# ir_array.net
KiCad netlist of a schematic drawn in Altium Designer
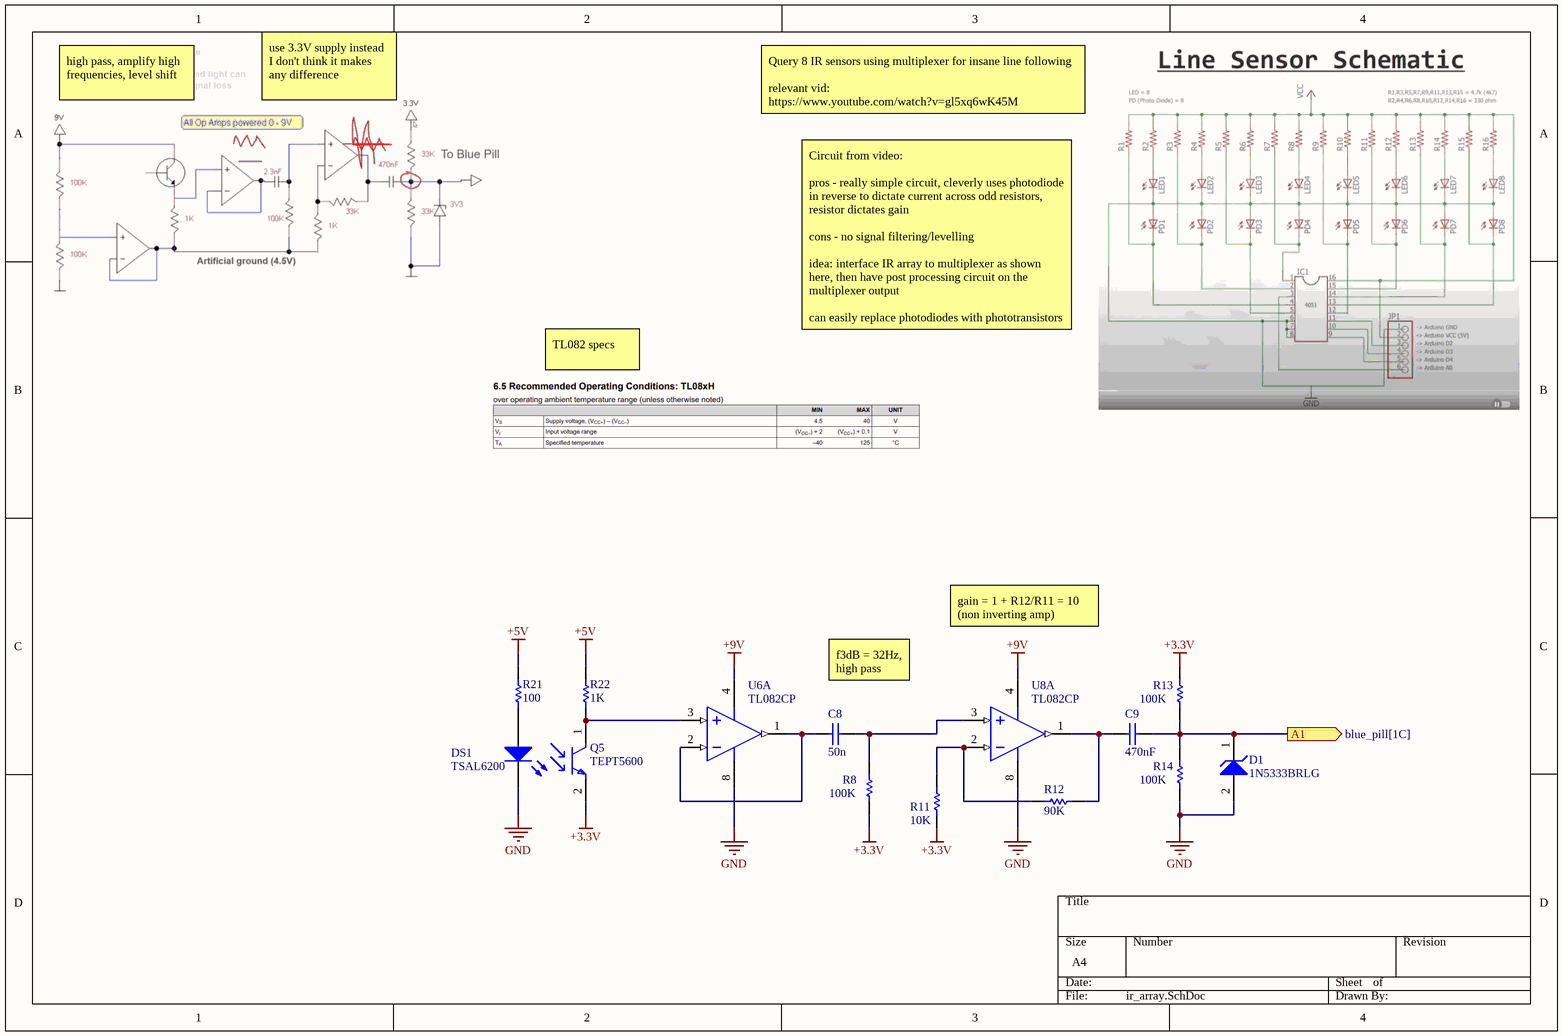
[diagram p0: ir_array.SchDoc]

(export (version "E")
  (design (tool "Eeschema 10.0.6"))
  (components
    (comp (ref "C8")
      (value "50n")
      (description "Capacitor")
      (libsource (lib "Simulation Generic Components") (part "Capacitor"))
    )
    (comp (ref "C9")
      (value "470nF")
      (description "Capacitor")
      (libsource (lib "Simulation Generic Components") (part "Capacitor"))
    )
    (comp (ref "D1")
      (value "1N5333BRLG")
      (footprint "ONSC-SURMETIC40-2-017AA-01")
      (description "5 W Zener Voltage Regulator, 2-Pin Surmetic(TM) 40, Pb-Free, Tape and Reel")
      (fields (field (name "MANUFACTURER") "On Semiconductor"))
      (libsource (lib "Altium Content Vault") (part "ONSC-K1A2-2"))
    )
    (comp (ref "DS1")
      (value "TSAL6200")
      (footprint "VISH-TSAL6200")
      (fields (field (name "MANUFACTURER") "Vishay"))
      (libsource (lib "Altium Content Vault") (part "LED-AK-2"))
    )
    (comp (ref "Q5")
      (value "TEPT5600")
      (footprint "FP-6_544-5185_03-4-MFG")
      (description "SENSOR PHOTO 570NM TOP VIEW RAD")
      (libsource (lib "Altium Content Vault") (part "9456f77f46cf90b3cfae45295d5ca59"))
    )
    (comp (ref "R8")
      (value "100K")
      (description "Resistor")
      (libsource (lib "Simulation Generic Components") (part "Resistor"))
    )
    (comp (ref "R11")
      (value "10K")
      (description "Resistor")
      (libsource (lib "Simulation Generic Components") (part "Resistor"))
    )
    (comp (ref "R12")
      (value "90K")
      (description "Resistor")
      (libsource (lib "Simulation Generic Components") (part "Resistor"))
    )
    (comp (ref "R13")
      (value "100K")
      (description "Resistor")
      (libsource (lib "Simulation Generic Components") (part "Resistor"))
    )
    (comp (ref "R14")
      (value "100K")
      (description "Resistor")
      (libsource (lib "Simulation Generic Components") (part "Resistor"))
    )
    (comp (ref "R21")
      (value "100")
      (description "Resistor")
      (libsource (lib "Simulation Generic Components") (part "Resistor"))
    )
    (comp (ref "R22")
      (value "1K")
      (description "Resistor")
      (libsource (lib "Simulation Generic Components") (part "Resistor"))
    )
    (comp (ref "U6")
      (value "TL082CP")
      (footprint "P0008A")
      (description "JFET-Input Operational Amplifier, 7 to 36 V, 0 to 70 degC, 8-pin DIP (P8), Pb-Free (RoHS)")
      (fields (field (name "MANUFACTURER") "Texas Instruments"))
      (libsource (lib "Altium Content Vault") (part "TI-AMP-D6-2-8_D"))
    )
    (comp (ref "U8")
      (value "TL082CP")
      (footprint "P0008A")
      (description "JFET-Input Operational Amplifier, 7 to 36 V, 0 to 70 degC, 8-pin DIP (P8), Pb-Free (RoHS)")
      (fields (field (name "MANUFACTURER") "Texas Instruments"))
      (libsource (lib "Altium Content Vault") (part "TI-AMP-D6-2-8_D"))
    )
  )
  (nets
    (net (code "1") (name "+3.3V") (class "Default")
      (node (ref "Q5") (pin "2") (pinfunction "E_2") (pintype "passive"))
      (node (ref "R11") (pin "2") (pinfunction "2_2") (pintype "passive"))
      (node (ref "R13") (pin "1") (pinfunction "1_1") (pintype "passive"))
      (node (ref "R8") (pin "2") (pinfunction "2_2") (pintype "passive"))
    )
    (net (code "2") (name "+5V") (class "Default")
      (node (ref "R21") (pin "1") (pinfunction "1_1") (pintype "passive"))
      (node (ref "R22") (pin "1") (pinfunction "1_1") (pintype "passive"))
    )
    (net (code "3") (name "+9V") (class "Default")
      (node (ref "U6") (pin "4") (pinfunction "VCC-_4") (pintype "power_in"))
      (node (ref "U8") (pin "4") (pinfunction "VCC-_4") (pintype "power_in"))
    )
    (net (code "4") (name "/A1") (class "Default")
      (node (ref "C9") (pin "2") (pinfunction "2_2") (pintype "passive"))
      (node (ref "D1") (pin "1") (pinfunction "K_1") (pintype "passive"))
      (node (ref "R13") (pin "2") (pinfunction "2_2") (pintype "passive"))
      (node (ref "R14") (pin "1") (pinfunction "1_1") (pintype "passive"))
    )
    (net (code "5") (name "GND") (class "Default")
      (node (ref "D1") (pin "2") (pinfunction "A_2") (pintype "passive"))
      (node (ref "DS1") (pin "2") (pinfunction "K_2") (pintype "passive"))
      (node (ref "R14") (pin "2") (pinfunction "2_2") (pintype "passive"))
      (node (ref "U6") (pin "8") (pinfunction "VCC+_8") (pintype "power_in"))
      (node (ref "U8") (pin "8") (pinfunction "VCC+_8") (pintype "power_in"))
    )
    (net (code "6") (name "Net-(DS1-A)") (class "Default")
      (node (ref "DS1") (pin "1") (pinfunction "A_1") (pintype "passive"))
      (node (ref "R21") (pin "2") (pinfunction "2_2") (pintype "passive"))
    )
    (net (code "7") (name "Net-(Q5-C)") (class "Default")
      (node (ref "Q5") (pin "1") (pinfunction "C_1") (pintype "passive"))
      (node (ref "R22") (pin "2") (pinfunction "2_2") (pintype "passive"))
      (node (ref "U6") (pin "3") (pinfunction "IN1+_3") (pintype "input"))
    )
    (net (code "8") (name "Net-(U6A-IN1-)") (class "Default")
      (node (ref "C8") (pin "1") (pinfunction "1_1") (pintype "passive"))
      (node (ref "U6") (pin "1") (pinfunction "OUT1_1") (pintype "output"))
      (node (ref "U6") (pin "2") (pinfunction "IN1-_2") (pintype "input"))
    )
    (net (code "9") (name "Net-(U8A-IN1+)") (class "Default")
      (node (ref "C8") (pin "2") (pinfunction "2_2") (pintype "passive"))
      (node (ref "R8") (pin "1") (pinfunction "1_1") (pintype "passive"))
      (node (ref "U8") (pin "3") (pinfunction "IN1+_3") (pintype "input"))
    )
    (net (code "10") (name "Net-(U8A-IN1-)") (class "Default")
      (node (ref "R11") (pin "1") (pinfunction "1_1") (pintype "passive"))
      (node (ref "R12") (pin "2") (pinfunction "2_2") (pintype "passive"))
      (node (ref "U8") (pin "2") (pinfunction "IN1-_2") (pintype "input"))
    )
    (net (code "11") (name "Net-(U8A-OUT1)") (class "Default")
      (node (ref "C9") (pin "1") (pinfunction "1_1") (pintype "passive"))
      (node (ref "R12") (pin "1") (pinfunction "1_1") (pintype "passive"))
      (node (ref "U8") (pin "1") (pinfunction "OUT1_1") (pintype "output"))
    )
  )
)
